# Sheet1.net
KiCad netlist of a schematic drawn in Altium Designer
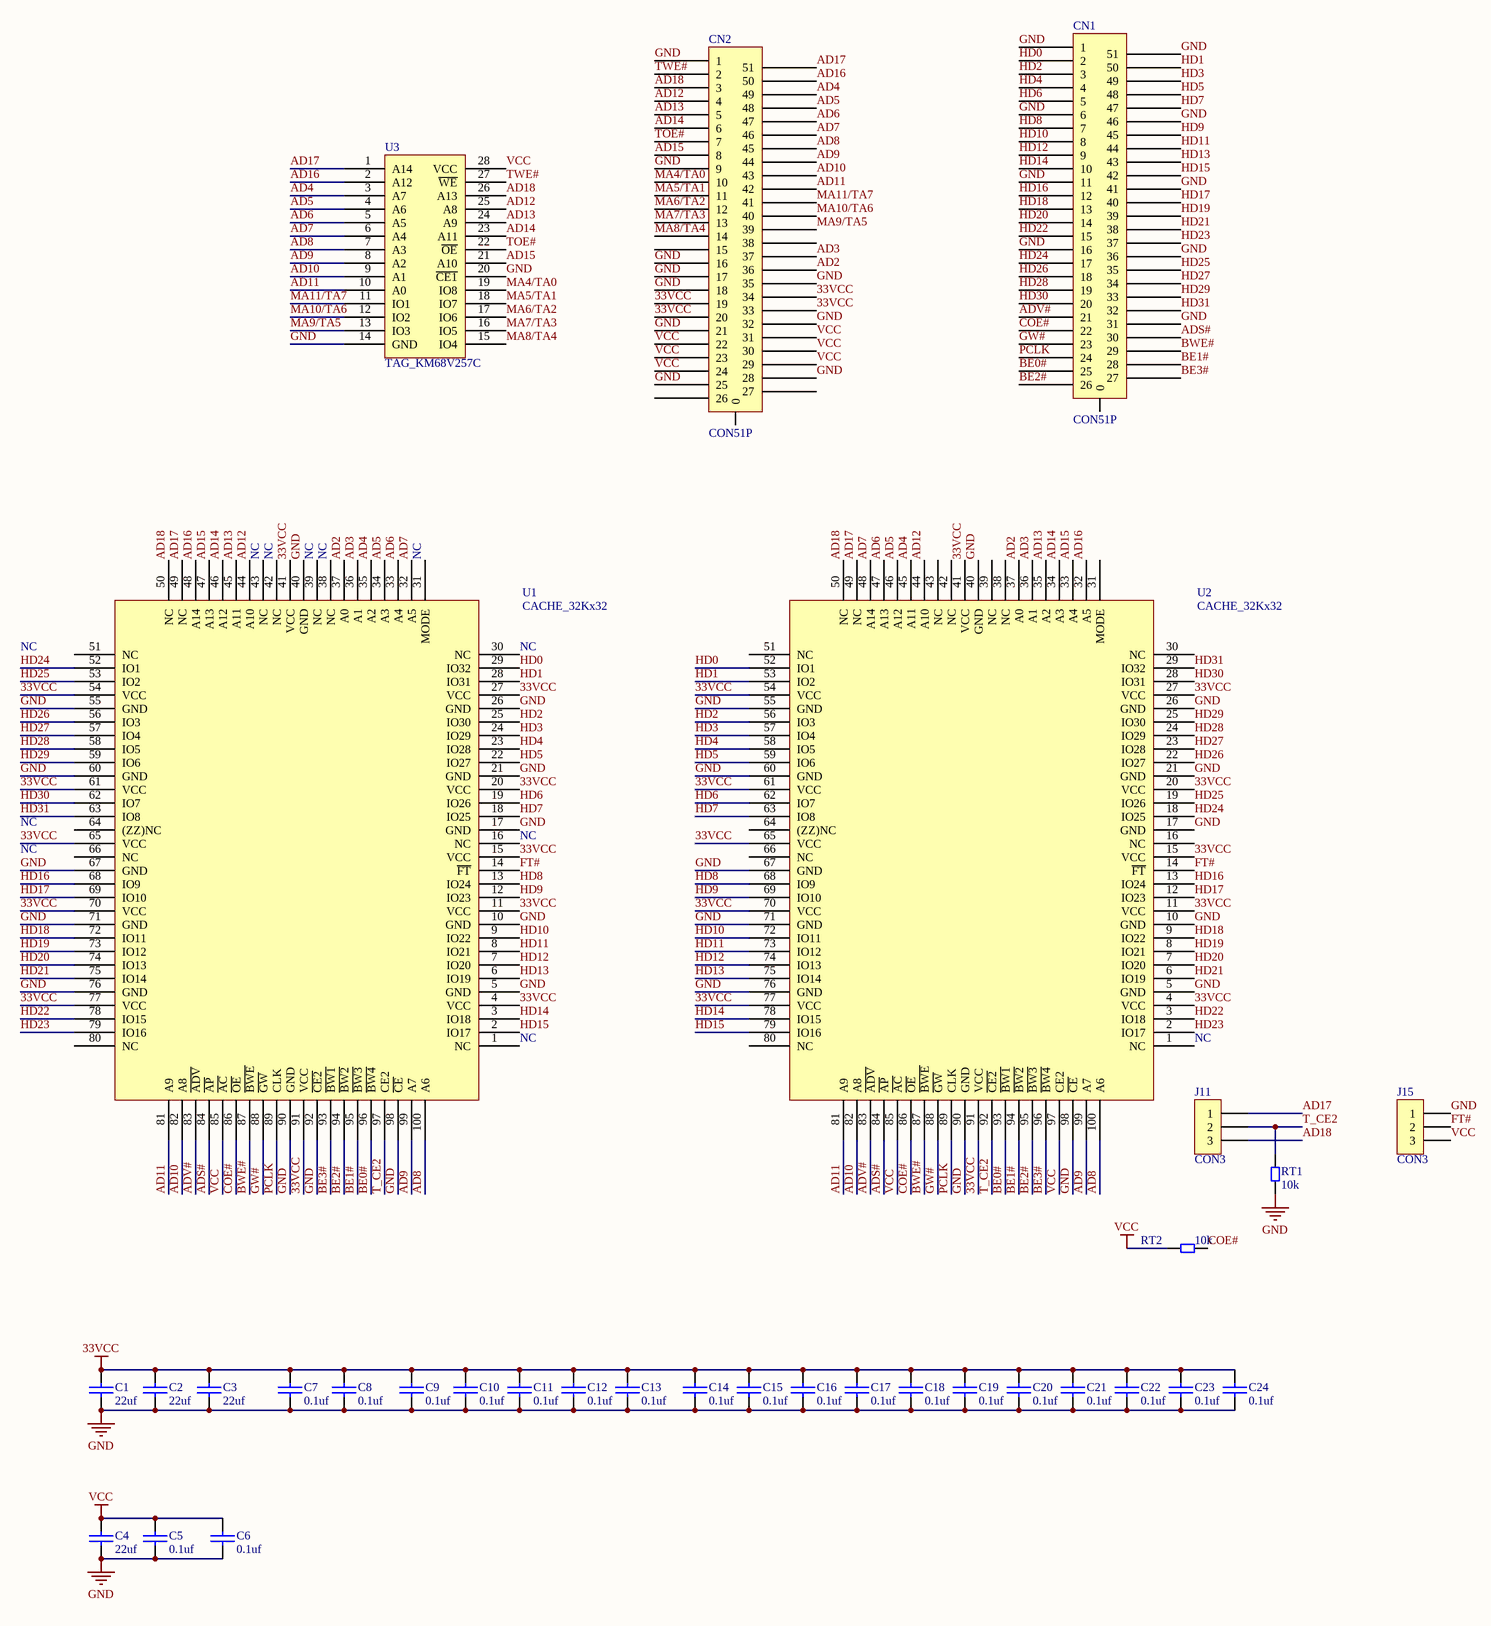
[diagram p0: Sheet1.SchDoc]

(export (version "E")
  (design (tool "Eeschema 10.0.6"))
  (components
    (comp (ref "C1") (value "22uf") (footprint "C0603") (libsource (lib "电阻电容二极管") (part "CAP")))
    (comp (ref "C2") (value "22uf") (footprint "C0603") (libsource (lib "电阻电容二极管") (part "CAP")))
    (comp (ref "C3") (value "22uf") (footprint "C0603") (libsource (lib "电阻电容二极管") (part "CAP")))
    (comp (ref "C4") (value "22uf") (footprint "C0603") (libsource (lib "电阻电容二极管") (part "CAP")))
    (comp (ref "C5") (value "0.1uf") (footprint "C0603") (libsource (lib "电阻电容二极管") (part "CAP")))
    (comp (ref "C6") (value "0.1uf") (footprint "C0603") (libsource (lib "电阻电容二极管") (part "CAP")))
    (comp (ref "C7") (value "0.1uf") (footprint "C0603") (libsource (lib "电阻电容二极管") (part "CAP")))
    (comp (ref "C8") (value "0.1uf") (footprint "C0603") (libsource (lib "电阻电容二极管") (part "CAP")))
    (comp (ref "C9") (value "0.1uf") (footprint "C0603") (libsource (lib "电阻电容二极管") (part "CAP")))
    (comp (ref "C10") (value "0.1uf") (footprint "C0603") (libsource (lib "电阻电容二极管") (part "CAP")))
    (comp (ref "C11") (value "0.1uf") (footprint "C0603") (libsource (lib "电阻电容二极管") (part "CAP")))
    (comp (ref "C12") (value "0.1uf") (footprint "C0603") (libsource (lib "电阻电容二极管") (part "CAP")))
    (comp (ref "C13") (value "0.1uf") (footprint "C0603") (libsource (lib "电阻电容二极管") (part "CAP")))
    (comp (ref "C14") (value "0.1uf") (footprint "C0603") (libsource (lib "电阻电容二极管") (part "CAP")))
    (comp (ref "C15") (value "0.1uf") (footprint "C0603") (libsource (lib "电阻电容二极管") (part "CAP")))
    (comp (ref "C16") (value "0.1uf") (footprint "C0603") (libsource (lib "电阻电容二极管") (part "CAP")))
    (comp (ref "C17") (value "0.1uf") (footprint "C0603") (libsource (lib "电阻电容二极管") (part "CAP")))
    (comp (ref "C18") (value "0.1uf") (footprint "C0603") (libsource (lib "电阻电容二极管") (part "CAP")))
    (comp (ref "C19") (value "0.1uf") (footprint "C0603") (libsource (lib "电阻电容二极管") (part "CAP")))
    (comp (ref "C20") (value "0.1uf") (footprint "C0603") (libsource (lib "电阻电容二极管") (part "CAP")))
    (comp (ref "C21") (value "0.1uf") (footprint "C0603") (libsource (lib "电阻电容二极管") (part "CAP")))
    (comp (ref "C22") (value "0.1uf") (footprint "C0603") (libsource (lib "电阻电容二极管") (part "CAP")))
    (comp (ref "C23") (value "0.1uf") (footprint "C0603") (libsource (lib "电阻电容二极管") (part "CAP")))
    (comp (ref "C24") (value "0.1uf") (footprint "C0603") (libsource (lib "电阻电容二极管") (part "CAP")))
    (comp (ref "CN1") (value "CON51P") (footprint "BTB1.0-51P") (libsource (lib "常用元件库") (part "CON51P")))
    (comp (ref "CN2") (value "CON51P") (footprint "BTB1.0-51P") (libsource (lib "常用元件库") (part "CON51P")))
    (comp (ref "J11") (value "CON3") (footprint "JMP") (libsource (lib "常用元件库") (part "CON3")))
    (comp (ref "J15") (value "CON3") (footprint "JMP") (libsource (lib "常用元件库") (part "CON3")))
    (comp (ref "RT1") (value "10k") (footprint "R0603") (libsource (lib "电阻电容二极管") (part "RES2")))
    (comp (ref "RT2") (value "10k") (footprint "R0603") (libsource (lib "电阻电容二极管") (part "RES2")))
    (comp (ref "U1")
      (value "CACHE_32Kx32")
      (footprint "PQFP100B")
      (libsource (lib "微机原理") (part "CACHE_32Kx32"))
    )
    (comp (ref "U2")
      (value "CACHE_32Kx32")
      (footprint "PQFP100B")
      (libsource (lib "微机原理") (part "CACHE_32Kx32"))
    )
    (comp (ref "U3")
      (value "TAG_KM68V257C")
      (footprint "SOJ-28")
      (libsource (lib "微机原理") (part "TAG_KM68V257C"))
    )
  )
  (nets
    (net (code "1") (name "/AD2") (class "Default")
      (node (ref "CN2") (pin "36") (pinfunction "36_36") (pintype "passive"))
      (node (ref "U1") (pin "37") (pinfunction "A0_37") (pintype "passive"))
      (node (ref "U2") (pin "37") (pinfunction "A0_37") (pintype "passive"))
    )
    (net (code "2") (name "/AD3") (class "Default")
      (node (ref "CN2") (pin "37") (pinfunction "37_37") (pintype "passive"))
      (node (ref "U1") (pin "36") (pinfunction "A1_36") (pintype "passive"))
      (node (ref "U2") (pin "36") (pinfunction "A1_36") (pintype "passive"))
    )
    (net (code "3") (name "/AD4") (class "Default")
      (node (ref "CN2") (pin "49") (pinfunction "49_49") (pintype "passive"))
      (node (ref "U1") (pin "35") (pinfunction "A2_35") (pintype "passive"))
      (node (ref "U2") (pin "45") (pinfunction "A11_45") (pintype "passive"))
      (node (ref "U3") (pin "3") (pinfunction "A7_3") (pintype "passive"))
    )
    (net (code "4") (name "/AD5") (class "Default")
      (node (ref "CN2") (pin "48") (pinfunction "48_48") (pintype "passive"))
      (node (ref "U1") (pin "34") (pinfunction "A3_34") (pintype "passive"))
      (node (ref "U2") (pin "46") (pinfunction "A12_46") (pintype "passive"))
      (node (ref "U3") (pin "4") (pinfunction "A6_4") (pintype "passive"))
    )
    (net (code "5") (name "/AD6") (class "Default")
      (node (ref "CN2") (pin "47") (pinfunction "47_47") (pintype "passive"))
      (node (ref "U1") (pin "33") (pinfunction "A4_33") (pintype "passive"))
      (node (ref "U2") (pin "47") (pinfunction "A13_47") (pintype "passive"))
      (node (ref "U3") (pin "5") (pinfunction "A5_5") (pintype "passive"))
    )
    (net (code "6") (name "/AD7") (class "Default")
      (node (ref "CN2") (pin "46") (pinfunction "46_46") (pintype "passive"))
      (node (ref "U1") (pin "32") (pinfunction "A5_32") (pintype "passive"))
      (node (ref "U2") (pin "48") (pinfunction "A14_48") (pintype "passive"))
      (node (ref "U3") (pin "6") (pinfunction "A4_6") (pintype "passive"))
    )
    (net (code "7") (name "/AD8") (class "Default")
      (node (ref "CN2") (pin "45") (pinfunction "45_45") (pintype "passive"))
      (node (ref "U1") (pin "100") (pinfunction "A6_100") (pintype "passive"))
      (node (ref "U2") (pin "100") (pinfunction "A6_100") (pintype "passive"))
      (node (ref "U3") (pin "7") (pinfunction "A3_7") (pintype "passive"))
    )
    (net (code "8") (name "/AD9") (class "Default")
      (node (ref "CN2") (pin "44") (pinfunction "44_44") (pintype "passive"))
      (node (ref "U1") (pin "99") (pinfunction "A7_99") (pintype "passive"))
      (node (ref "U2") (pin "99") (pinfunction "A7_99") (pintype "passive"))
      (node (ref "U3") (pin "8") (pinfunction "A2_8") (pintype "passive"))
    )
    (net (code "9") (name "/AD10") (class "Default")
      (node (ref "CN2") (pin "43") (pinfunction "43_43") (pintype "passive"))
      (node (ref "U1") (pin "82") (pinfunction "A8_82") (pintype "passive"))
      (node (ref "U2") (pin "82") (pinfunction "A8_82") (pintype "passive"))
      (node (ref "U3") (pin "9") (pinfunction "A1_9") (pintype "passive"))
    )
    (net (code "10") (name "/AD11") (class "Default")
      (node (ref "CN2") (pin "42") (pinfunction "42_42") (pintype "passive"))
      (node (ref "U1") (pin "81") (pinfunction "A9_81") (pintype "passive"))
      (node (ref "U2") (pin "81") (pinfunction "A9_81") (pintype "passive"))
      (node (ref "U3") (pin "10") (pinfunction "A0_10") (pintype "passive"))
    )
    (net (code "11") (name "/AD12") (class "Default")
      (node (ref "CN2") (pin "4") (pinfunction "4_4") (pintype "passive"))
      (node (ref "U1") (pin "44") (pinfunction "A10_44") (pintype "passive"))
      (node (ref "U2") (pin "44") (pinfunction "A10_44") (pintype "passive"))
      (node (ref "U3") (pin "25") (pinfunction "A8_25") (pintype "passive"))
    )
    (net (code "12") (name "/AD13") (class "Default")
      (node (ref "CN2") (pin "5") (pinfunction "5_5") (pintype "passive"))
      (node (ref "U1") (pin "45") (pinfunction "A11_45") (pintype "passive"))
      (node (ref "U2") (pin "35") (pinfunction "A2_35") (pintype "passive"))
      (node (ref "U3") (pin "24") (pinfunction "A9_24") (pintype "passive"))
    )
    (net (code "13") (name "/AD14") (class "Default")
      (node (ref "CN2") (pin "6") (pinfunction "6_6") (pintype "passive"))
      (node (ref "U1") (pin "46") (pinfunction "A12_46") (pintype "passive"))
      (node (ref "U2") (pin "34") (pinfunction "A3_34") (pintype "passive"))
      (node (ref "U3") (pin "23") (pinfunction "A11_23") (pintype "passive"))
    )
    (net (code "14") (name "/AD15") (class "Default")
      (node (ref "CN2") (pin "8") (pinfunction "8_8") (pintype "passive"))
      (node (ref "U1") (pin "47") (pinfunction "A13_47") (pintype "passive"))
      (node (ref "U2") (pin "33") (pinfunction "A4_33") (pintype "passive"))
      (node (ref "U3") (pin "21") (pinfunction "A10_21") (pintype "passive"))
    )
    (net (code "15") (name "/AD16") (class "Default")
      (node (ref "CN2") (pin "50") (pinfunction "50_50") (pintype "passive"))
      (node (ref "U1") (pin "48") (pinfunction "A14_48") (pintype "passive"))
      (node (ref "U2") (pin "32") (pinfunction "A5_32") (pintype "passive"))
      (node (ref "U3") (pin "2") (pinfunction "A12_2") (pintype "passive"))
    )
    (net (code "16") (name "/AD17") (class "Default")
      (node (ref "CN2") (pin "51") (pinfunction "51_51") (pintype "passive"))
      (node (ref "J11") (pin "1") (pinfunction "1_1") (pintype "passive"))
      (node (ref "U1") (pin "49") (pinfunction "NC_49") (pintype "passive"))
      (node (ref "U2") (pin "49") (pinfunction "NC_49") (pintype "passive"))
      (node (ref "U3") (pin "1") (pinfunction "A14_1") (pintype "passive"))
    )
    (net (code "17") (name "/AD18") (class "Default")
      (node (ref "CN2") (pin "3") (pinfunction "3_3") (pintype "passive"))
      (node (ref "J11") (pin "3") (pinfunction "3_3") (pintype "passive"))
      (node (ref "U1") (pin "50") (pinfunction "NC_50") (pintype "passive"))
      (node (ref "U2") (pin "50") (pinfunction "NC_50") (pintype "passive"))
      (node (ref "U3") (pin "26") (pinfunction "A13_26") (pintype "passive"))
    )
    (net (code "18") (name "/ADS#") (class "Default")
      (node (ref "CN1") (pin "30") (pinfunction "30_30") (pintype "passive"))
      (node (ref "U1") (pin "84") (pinfunction "~{AP}_84") (pintype "passive"))
      (node (ref "U2") (pin "84") (pinfunction "~{AP}_84") (pintype "passive"))
    )
    (net (code "19") (name "/ADV#") (class "Default")
      (node (ref "CN1") (pin "21") (pinfunction "21_21") (pintype "passive"))
      (node (ref "U1") (pin "83") (pinfunction "~{ADV}_83") (pintype "passive"))
      (node (ref "U2") (pin "83") (pinfunction "~{ADV}_83") (pintype "passive"))
    )
    (net (code "20") (name "/BE0#") (class "Default")
      (node (ref "CN1") (pin "25") (pinfunction "25_25") (pintype "passive"))
      (node (ref "U1") (pin "96") (pinfunction "~{BW4}_96") (pintype "passive"))
      (node (ref "U2") (pin "93") (pinfunction "~{BW1}_93") (pintype "passive"))
    )
    (net (code "21") (name "/BE1#") (class "Default")
      (node (ref "CN1") (pin "28") (pinfunction "28_28") (pintype "passive"))
      (node (ref "U1") (pin "95") (pinfunction "~{BW3}_95") (pintype "passive"))
      (node (ref "U2") (pin "94") (pinfunction "~{BW2}_94") (pintype "passive"))
    )
    (net (code "22") (name "/BE2#") (class "Default")
      (node (ref "CN1") (pin "26") (pinfunction "26_26") (pintype "passive"))
      (node (ref "U1") (pin "94") (pinfunction "~{BW2}_94") (pintype "passive"))
      (node (ref "U2") (pin "95") (pinfunction "~{BW3}_95") (pintype "passive"))
    )
    (net (code "23") (name "/BE3#") (class "Default")
      (node (ref "CN1") (pin "27") (pinfunction "27_27") (pintype "passive"))
      (node (ref "U1") (pin "93") (pinfunction "~{BW1}_93") (pintype "passive"))
      (node (ref "U2") (pin "96") (pinfunction "~{BW4}_96") (pintype "passive"))
    )
    (net (code "24") (name "/BWE#") (class "Default")
      (node (ref "CN1") (pin "29") (pinfunction "29_29") (pintype "passive"))
      (node (ref "U1") (pin "87") (pinfunction "~{BWE}_87") (pintype "passive"))
      (node (ref "U2") (pin "87") (pinfunction "~{BWE}_87") (pintype "passive"))
    )
    (net (code "25") (name "/COE#") (class "Default")
      (node (ref "CN1") (pin "22") (pinfunction "22_22") (pintype "passive"))
      (node (ref "RT2") (pin "1") (pinfunction "1_1") (pintype "passive"))
      (node (ref "U1") (pin "86") (pinfunction "~{OE}_86") (pintype "passive"))
      (node (ref "U2") (pin "86") (pinfunction "~{OE}_86") (pintype "passive"))
    )
    (net (code "26") (name "/FT#") (class "Default")
      (node (ref "J15") (pin "2") (pinfunction "2_2") (pintype "passive"))
      (node (ref "U1") (pin "14") (pinfunction "~{FT}_14") (pintype "passive"))
      (node (ref "U2") (pin "14") (pinfunction "~{FT}_14") (pintype "passive"))
    )
    (net (code "27") (name "/GW#") (class "Default")
      (node (ref "CN1") (pin "23") (pinfunction "23_23") (pintype "passive"))
      (node (ref "U1") (pin "88") (pinfunction "~{GW}_88") (pintype "passive"))
      (node (ref "U2") (pin "88") (pinfunction "~{GW}_88") (pintype "passive"))
    )
    (net (code "28") (name "/HD0") (class "Default")
      (node (ref "CN1") (pin "2") (pinfunction "2_2") (pintype "passive"))
      (node (ref "U1") (pin "29") (pinfunction "IO32_29") (pintype "passive"))
      (node (ref "U2") (pin "52") (pinfunction "IO1_52") (pintype "passive"))
    )
    (net (code "29") (name "/HD1") (class "Default")
      (node (ref "CN1") (pin "50") (pinfunction "50_50") (pintype "passive"))
      (node (ref "U1") (pin "28") (pinfunction "IO31_28") (pintype "passive"))
      (node (ref "U2") (pin "53") (pinfunction "IO2_53") (pintype "passive"))
    )
    (net (code "30") (name "/HD2") (class "Default")
      (node (ref "CN1") (pin "3") (pinfunction "3_3") (pintype "passive"))
      (node (ref "U1") (pin "25") (pinfunction "IO30_25") (pintype "passive"))
      (node (ref "U2") (pin "56") (pinfunction "IO3_56") (pintype "passive"))
    )
    (net (code "31") (name "/HD3") (class "Default")
      (node (ref "CN1") (pin "49") (pinfunction "49_49") (pintype "passive"))
      (node (ref "U1") (pin "24") (pinfunction "IO29_24") (pintype "passive"))
      (node (ref "U2") (pin "57") (pinfunction "IO4_57") (pintype "passive"))
    )
    (net (code "32") (name "/HD4") (class "Default")
      (node (ref "CN1") (pin "4") (pinfunction "4_4") (pintype "passive"))
      (node (ref "U1") (pin "23") (pinfunction "IO28_23") (pintype "passive"))
      (node (ref "U2") (pin "58") (pinfunction "IO5_58") (pintype "passive"))
    )
    (net (code "33") (name "/HD5") (class "Default")
      (node (ref "CN1") (pin "48") (pinfunction "48_48") (pintype "passive"))
      (node (ref "U1") (pin "22") (pinfunction "IO27_22") (pintype "passive"))
      (node (ref "U2") (pin "59") (pinfunction "IO6_59") (pintype "passive"))
    )
    (net (code "34") (name "/HD6") (class "Default")
      (node (ref "CN1") (pin "5") (pinfunction "5_5") (pintype "passive"))
      (node (ref "U1") (pin "19") (pinfunction "IO26_19") (pintype "passive"))
      (node (ref "U2") (pin "62") (pinfunction "IO7_62") (pintype "passive"))
    )
    (net (code "35") (name "/HD7") (class "Default")
      (node (ref "CN1") (pin "47") (pinfunction "47_47") (pintype "passive"))
      (node (ref "U1") (pin "18") (pinfunction "IO25_18") (pintype "passive"))
      (node (ref "U2") (pin "63") (pinfunction "IO8_63") (pintype "passive"))
    )
    (net (code "36") (name "/HD8") (class "Default")
      (node (ref "CN1") (pin "7") (pinfunction "7_7") (pintype "passive"))
      (node (ref "U1") (pin "13") (pinfunction "IO24_13") (pintype "passive"))
      (node (ref "U2") (pin "68") (pinfunction "IO9_68") (pintype "passive"))
    )
    (net (code "37") (name "/HD9") (class "Default")
      (node (ref "CN1") (pin "45") (pinfunction "45_45") (pintype "passive"))
      (node (ref "U1") (pin "12") (pinfunction "IO23_12") (pintype "passive"))
      (node (ref "U2") (pin "69") (pinfunction "IO10_69") (pintype "passive"))
    )
    (net (code "38") (name "/HD10") (class "Default")
      (node (ref "CN1") (pin "8") (pinfunction "8_8") (pintype "passive"))
      (node (ref "U1") (pin "9") (pinfunction "IO22_9") (pintype "passive"))
      (node (ref "U2") (pin "72") (pinfunction "IO11_72") (pintype "passive"))
    )
    (net (code "39") (name "/HD11") (class "Default")
      (node (ref "CN1") (pin "44") (pinfunction "44_44") (pintype "passive"))
      (node (ref "U1") (pin "8") (pinfunction "IO21_8") (pintype "passive"))
      (node (ref "U2") (pin "73") (pinfunction "IO12_73") (pintype "passive"))
    )
    (net (code "40") (name "/HD12") (class "Default")
      (node (ref "CN1") (pin "9") (pinfunction "9_9") (pintype "passive"))
      (node (ref "U1") (pin "7") (pinfunction "IO20_7") (pintype "passive"))
      (node (ref "U2") (pin "74") (pinfunction "IO13_74") (pintype "passive"))
    )
    (net (code "41") (name "/HD13") (class "Default")
      (node (ref "CN1") (pin "43") (pinfunction "43_43") (pintype "passive"))
      (node (ref "U1") (pin "6") (pinfunction "IO19_6") (pintype "passive"))
      (node (ref "U2") (pin "75") (pinfunction "IO14_75") (pintype "passive"))
    )
    (net (code "42") (name "/HD14") (class "Default")
      (node (ref "CN1") (pin "10") (pinfunction "10_10") (pintype "passive"))
      (node (ref "U1") (pin "3") (pinfunction "IO18_3") (pintype "passive"))
      (node (ref "U2") (pin "78") (pinfunction "IO15_78") (pintype "passive"))
    )
    (net (code "43") (name "/HD15") (class "Default")
      (node (ref "CN1") (pin "42") (pinfunction "42_42") (pintype "passive"))
      (node (ref "U1") (pin "2") (pinfunction "IO17_2") (pintype "passive"))
      (node (ref "U2") (pin "79") (pinfunction "IO16_79") (pintype "passive"))
    )
    (net (code "44") (name "/HD16") (class "Default")
      (node (ref "CN1") (pin "12") (pinfunction "12_12") (pintype "passive"))
      (node (ref "U1") (pin "68") (pinfunction "IO9_68") (pintype "passive"))
      (node (ref "U2") (pin "13") (pinfunction "IO24_13") (pintype "passive"))
    )
    (net (code "45") (name "/HD17") (class "Default")
      (node (ref "CN1") (pin "40") (pinfunction "40_40") (pintype "passive"))
      (node (ref "U1") (pin "69") (pinfunction "IO10_69") (pintype "passive"))
      (node (ref "U2") (pin "12") (pinfunction "IO23_12") (pintype "passive"))
    )
    (net (code "46") (name "/HD18") (class "Default")
      (node (ref "CN1") (pin "13") (pinfunction "13_13") (pintype "passive"))
      (node (ref "U1") (pin "72") (pinfunction "IO11_72") (pintype "passive"))
      (node (ref "U2") (pin "9") (pinfunction "IO22_9") (pintype "passive"))
    )
    (net (code "47") (name "/HD19") (class "Default")
      (node (ref "CN1") (pin "39") (pinfunction "39_39") (pintype "passive"))
      (node (ref "U1") (pin "73") (pinfunction "IO12_73") (pintype "passive"))
      (node (ref "U2") (pin "8") (pinfunction "IO21_8") (pintype "passive"))
    )
    (net (code "48") (name "/HD20") (class "Default")
      (node (ref "CN1") (pin "14") (pinfunction "14_14") (pintype "passive"))
      (node (ref "U1") (pin "74") (pinfunction "IO13_74") (pintype "passive"))
      (node (ref "U2") (pin "7") (pinfunction "IO20_7") (pintype "passive"))
    )
    (net (code "49") (name "/HD21") (class "Default")
      (node (ref "CN1") (pin "38") (pinfunction "38_38") (pintype "passive"))
      (node (ref "U1") (pin "75") (pinfunction "IO14_75") (pintype "passive"))
      (node (ref "U2") (pin "6") (pinfunction "IO19_6") (pintype "passive"))
    )
    (net (code "50") (name "/HD22") (class "Default")
      (node (ref "CN1") (pin "15") (pinfunction "15_15") (pintype "passive"))
      (node (ref "U1") (pin "78") (pinfunction "IO15_78") (pintype "passive"))
      (node (ref "U2") (pin "3") (pinfunction "IO18_3") (pintype "passive"))
    )
    (net (code "51") (name "/HD23") (class "Default")
      (node (ref "CN1") (pin "37") (pinfunction "37_37") (pintype "passive"))
      (node (ref "U1") (pin "79") (pinfunction "IO16_79") (pintype "passive"))
      (node (ref "U2") (pin "2") (pinfunction "IO17_2") (pintype "passive"))
    )
    (net (code "52") (name "/HD24") (class "Default")
      (node (ref "CN1") (pin "17") (pinfunction "17_17") (pintype "passive"))
      (node (ref "U1") (pin "52") (pinfunction "IO1_52") (pintype "passive"))
      (node (ref "U2") (pin "18") (pinfunction "IO25_18") (pintype "passive"))
    )
    (net (code "53") (name "/HD25") (class "Default")
      (node (ref "CN1") (pin "35") (pinfunction "35_35") (pintype "passive"))
      (node (ref "U1") (pin "53") (pinfunction "IO2_53") (pintype "passive"))
      (node (ref "U2") (pin "19") (pinfunction "IO26_19") (pintype "passive"))
    )
    (net (code "54") (name "/HD26") (class "Default")
      (node (ref "CN1") (pin "18") (pinfunction "18_18") (pintype "passive"))
      (node (ref "U1") (pin "56") (pinfunction "IO3_56") (pintype "passive"))
      (node (ref "U2") (pin "22") (pinfunction "IO27_22") (pintype "passive"))
    )
    (net (code "55") (name "/HD27") (class "Default")
      (node (ref "CN1") (pin "34") (pinfunction "34_34") (pintype "passive"))
      (node (ref "U1") (pin "57") (pinfunction "IO4_57") (pintype "passive"))
      (node (ref "U2") (pin "23") (pinfunction "IO28_23") (pintype "passive"))
    )
    (net (code "56") (name "/HD28") (class "Default")
      (node (ref "CN1") (pin "19") (pinfunction "19_19") (pintype "passive"))
      (node (ref "U1") (pin "58") (pinfunction "IO5_58") (pintype "passive"))
      (node (ref "U2") (pin "24") (pinfunction "IO29_24") (pintype "passive"))
    )
    (net (code "57") (name "/HD29") (class "Default")
      (node (ref "CN1") (pin "33") (pinfunction "33_33") (pintype "passive"))
      (node (ref "U1") (pin "59") (pinfunction "IO6_59") (pintype "passive"))
      (node (ref "U2") (pin "25") (pinfunction "IO30_25") (pintype "passive"))
    )
    (net (code "58") (name "/HD30") (class "Default")
      (node (ref "CN1") (pin "20") (pinfunction "20_20") (pintype "passive"))
      (node (ref "U1") (pin "62") (pinfunction "IO7_62") (pintype "passive"))
      (node (ref "U2") (pin "28") (pinfunction "IO31_28") (pintype "passive"))
    )
    (net (code "59") (name "/HD31") (class "Default")
      (node (ref "CN1") (pin "32") (pinfunction "32_32") (pintype "passive"))
      (node (ref "U1") (pin "63") (pinfunction "IO8_63") (pintype "passive"))
      (node (ref "U2") (pin "29") (pinfunction "IO32_29") (pintype "passive"))
    )
    (net (code "60") (name "/MA4{slash}TA0") (class "Default")
      (node (ref "CN2") (pin "10") (pinfunction "10_10") (pintype "passive"))
      (node (ref "U3") (pin "19") (pinfunction "IO8_19") (pintype "passive"))
    )
    (net (code "61") (name "/MA5{slash}TA1") (class "Default")
      (node (ref "CN2") (pin "11") (pinfunction "11_11") (pintype "passive"))
      (node (ref "U3") (pin "18") (pinfunction "IO7_18") (pintype "passive"))
    )
    (net (code "62") (name "/MA6{slash}TA2") (class "Default")
      (node (ref "CN2") (pin "12") (pinfunction "12_12") (pintype "passive"))
      (node (ref "U3") (pin "17") (pinfunction "IO6_17") (pintype "passive"))
    )
    (net (code "63") (name "/MA7{slash}TA3") (class "Default")
      (node (ref "CN2") (pin "13") (pinfunction "13_13") (pintype "passive"))
      (node (ref "U3") (pin "16") (pinfunction "IO5_16") (pintype "passive"))
    )
    (net (code "64") (name "/MA8{slash}TA4") (class "Default")
      (node (ref "CN2") (pin "14") (pinfunction "14_14") (pintype "passive"))
      (node (ref "U3") (pin "15") (pinfunction "IO4_15") (pintype "passive"))
    )
    (net (code "65") (name "/MA9{slash}TA5") (class "Default")
      (node (ref "CN2") (pin "39") (pinfunction "39_39") (pintype "passive"))
      (node (ref "U3") (pin "13") (pinfunction "IO3_13") (pintype "passive"))
    )
    (net (code "66") (name "/MA10{slash}TA6") (class "Default")
      (node (ref "CN2") (pin "40") (pinfunction "40_40") (pintype "passive"))
      (node (ref "U3") (pin "12") (pinfunction "IO2_12") (pintype "passive"))
    )
    (net (code "67") (name "/MA11{slash}TA7") (class "Default")
      (node (ref "CN2") (pin "41") (pinfunction "41_41") (pintype "passive"))
      (node (ref "U3") (pin "11") (pinfunction "IO1_11") (pintype "passive"))
    )
    (net (code "68") (name "/PCLK") (class "Default")
      (node (ref "CN1") (pin "24") (pinfunction "24_24") (pintype "passive"))
      (node (ref "U1") (pin "89") (pinfunction "CLK_89") (pintype "passive"))
      (node (ref "U2") (pin "89") (pinfunction "CLK_89") (pintype "passive"))
    )
    (net (code "69") (name "/TOE#") (class "Default")
      (node (ref "CN2") (pin "7") (pinfunction "7_7") (pintype "passive"))
      (node (ref "U3") (pin "22") (pinfunction "~{OE}_22") (pintype "passive"))
    )
    (net (code "70") (name "/TWE#") (class "Default")
      (node (ref "CN2") (pin "2") (pinfunction "2_2") (pintype "passive"))
      (node (ref "U3") (pin "27") (pinfunction "~{WE}_27") (pintype "passive"))
    )
    (net (code "71") (name "/T_CE2") (class "Default")
      (node (ref "J11") (pin "2") (pinfunction "2_2") (pintype "passive"))
      (node (ref "RT1") (pin "1") (pinfunction "1_1") (pintype "passive"))
      (node (ref "U1") (pin "97") (pinfunction "CE2_97") (pintype "passive"))
      (node (ref "U2") (pin "92") (pinfunction "~{CE2}_92") (pintype "passive"))
    )
    (net (code "72") (name "33VCC") (class "Default")
      (node (ref "C1") (pin "1") (pinfunction "1_1") (pintype "passive"))
      (node (ref "C10") (pin "1") (pinfunction "1_1") (pintype "passive"))
      (node (ref "C11") (pin "1") (pinfunction "1_1") (pintype "passive"))
      (node (ref "C12") (pin "1") (pinfunction "1_1") (pintype "passive"))
      (node (ref "C13") (pin "1") (pinfunction "1_1") (pintype "passive"))
      (node (ref "C14") (pin "1") (pinfunction "1_1") (pintype "passive"))
      (node (ref "C15") (pin "1") (pinfunction "1_1") (pintype "passive"))
      (node (ref "C16") (pin "1") (pinfunction "1_1") (pintype "passive"))
      (node (ref "C17") (pin "1") (pinfunction "1_1") (pintype "passive"))
      (node (ref "C18") (pin "1") (pinfunction "1_1") (pintype "passive"))
      (node (ref "C19") (pin "1") (pinfunction "1_1") (pintype "passive"))
      (node (ref "C2") (pin "1") (pinfunction "1_1") (pintype "passive"))
      (node (ref "C20") (pin "1") (pinfunction "1_1") (pintype "passive"))
      (node (ref "C21") (pin "1") (pinfunction "1_1") (pintype "passive"))
      (node (ref "C22") (pin "1") (pinfunction "1_1") (pintype "passive"))
      (node (ref "C23") (pin "1") (pinfunction "1_1") (pintype "passive"))
      (node (ref "C24") (pin "1") (pinfunction "1_1") (pintype "passive"))
      (node (ref "C3") (pin "1") (pinfunction "1_1") (pintype "passive"))
      (node (ref "C7") (pin "1") (pinfunction "1_1") (pintype "passive"))
      (node (ref "C8") (pin "1") (pinfunction "1_1") (pintype "passive"))
      (node (ref "C9") (pin "1") (pinfunction "1_1") (pintype "passive"))
      (node (ref "CN2") (pin "19") (pinfunction "19_19") (pintype "passive"))
      (node (ref "CN2") (pin "20") (pinfunction "20_20") (pintype "passive"))
      (node (ref "CN2") (pin "33") (pinfunction "33_33") (pintype "passive"))
      (node (ref "CN2") (pin "34") (pinfunction "34_34") (pintype "passive"))
      (node (ref "U1") (pin "11") (pinfunction "VCC_11") (pintype "passive"))
      (node (ref "U1") (pin "15") (pinfunction "VCC_15") (pintype "passive"))
      (node (ref "U1") (pin "20") (pinfunction "VCC_20") (pintype "passive"))
      (node (ref "U1") (pin "27") (pinfunction "VCC_27") (pintype "passive"))
      (node (ref "U1") (pin "4") (pinfunction "VCC_4") (pintype "passive"))
      (node (ref "U1") (pin "41") (pinfunction "VCC_41") (pintype "passive"))
      (node (ref "U1") (pin "54") (pinfunction "VCC_54") (pintype "passive"))
      (node (ref "U1") (pin "61") (pinfunction "VCC_61") (pintype "passive"))
      (node (ref "U1") (pin "65") (pinfunction "VCC_65") (pintype "passive"))
      (node (ref "U1") (pin "70") (pinfunction "VCC_70") (pintype "passive"))
      (node (ref "U1") (pin "77") (pinfunction "VCC_77") (pintype "passive"))
      (node (ref "U1") (pin "91") (pinfunction "VCC_91") (pintype "passive"))
      (node (ref "U2") (pin "11") (pinfunction "VCC_11") (pintype "passive"))
      (node (ref "U2") (pin "15") (pinfunction "VCC_15") (pintype "passive"))
      (node (ref "U2") (pin "20") (pinfunction "VCC_20") (pintype "passive"))
      (node (ref "U2") (pin "27") (pinfunction "VCC_27") (pintype "passive"))
      (node (ref "U2") (pin "4") (pinfunction "VCC_4") (pintype "passive"))
      (node (ref "U2") (pin "41") (pinfunction "VCC_41") (pintype "passive"))
      (node (ref "U2") (pin "54") (pinfunction "VCC_54") (pintype "passive"))
      (node (ref "U2") (pin "61") (pinfunction "VCC_61") (pintype "passive"))
      (node (ref "U2") (pin "65") (pinfunction "VCC_65") (pintype "passive"))
      (node (ref "U2") (pin "70") (pinfunction "VCC_70") (pintype "passive"))
      (node (ref "U2") (pin "77") (pinfunction "VCC_77") (pintype "passive"))
      (node (ref "U2") (pin "91") (pinfunction "VCC_91") (pintype "passive"))
    )
    (net (code "73") (name "GND") (class "Default")
      (node (ref "C1") (pin "2") (pinfunction "2_2") (pintype "passive"))
      (node (ref "C10") (pin "2") (pinfunction "2_2") (pintype "passive"))
      (node (ref "C11") (pin "2") (pinfunction "2_2") (pintype "passive"))
      (node (ref "C12") (pin "2") (pinfunction "2_2") (pintype "passive"))
      (node (ref "C13") (pin "2") (pinfunction "2_2") (pintype "passive"))
      (node (ref "C14") (pin "2") (pinfunction "2_2") (pintype "passive"))
      (node (ref "C15") (pin "2") (pinfunction "2_2") (pintype "passive"))
      (node (ref "C16") (pin "2") (pinfunction "2_2") (pintype "passive"))
      (node (ref "C17") (pin "2") (pinfunction "2_2") (pintype "passive"))
      (node (ref "C18") (pin "2") (pinfunction "2_2") (pintype "passive"))
      (node (ref "C19") (pin "2") (pinfunction "2_2") (pintype "passive"))
      (node (ref "C2") (pin "2") (pinfunction "2_2") (pintype "passive"))
      (node (ref "C20") (pin "2") (pinfunction "2_2") (pintype "passive"))
      (node (ref "C21") (pin "2") (pinfunction "2_2") (pintype "passive"))
      (node (ref "C22") (pin "2") (pinfunction "2_2") (pintype "passive"))
      (node (ref "C23") (pin "2") (pinfunction "2_2") (pintype "passive"))
      (node (ref "C24") (pin "2") (pinfunction "2_2") (pintype "passive"))
      (node (ref "C3") (pin "2") (pinfunction "2_2") (pintype "passive"))
      (node (ref "C4") (pin "2") (pinfunction "2_2") (pintype "passive"))
      (node (ref "C5") (pin "2") (pinfunction "2_2") (pintype "passive"))
      (node (ref "C6") (pin "2") (pinfunction "2_2") (pintype "passive"))
      (node (ref "C7") (pin "2") (pinfunction "2_2") (pintype "passive"))
      (node (ref "C8") (pin "2") (pinfunction "2_2") (pintype "passive"))
      (node (ref "C9") (pin "2") (pinfunction "2_2") (pintype "passive"))
      (node (ref "CN1") (pin "1") (pinfunction "1_1") (pintype "passive"))
      (node (ref "CN1") (pin "11") (pinfunction "11_11") (pintype "passive"))
      (node (ref "CN1") (pin "16") (pinfunction "16_16") (pintype "passive"))
      (node (ref "CN1") (pin "31") (pinfunction "31_31") (pintype "passive"))
      (node (ref "CN1") (pin "36") (pinfunction "36_36") (pintype "passive"))
      (node (ref "CN1") (pin "41") (pinfunction "41_41") (pintype "passive"))
      (node (ref "CN1") (pin "46") (pinfunction "46_46") (pintype "passive"))
      (node (ref "CN1") (pin "51") (pinfunction "51_51") (pintype "passive"))
      (node (ref "CN1") (pin "6") (pinfunction "6_6") (pintype "passive"))
      (node (ref "CN2") (pin "1") (pinfunction "1_1") (pintype "passive"))
      (node (ref "CN2") (pin "16") (pinfunction "16_16") (pintype "passive"))
      (node (ref "CN2") (pin "17") (pinfunction "17_17") (pintype "passive"))
      (node (ref "CN2") (pin "18") (pinfunction "18_18") (pintype "passive"))
      (node (ref "CN2") (pin "21") (pinfunction "21_21") (pintype "passive"))
      (node (ref "CN2") (pin "25") (pinfunction "25_25") (pintype "passive"))
      (node (ref "CN2") (pin "28") (pinfunction "28_28") (pintype "passive"))
      (node (ref "CN2") (pin "32") (pinfunction "32_32") (pintype "passive"))
      (node (ref "CN2") (pin "35") (pinfunction "35_35") (pintype "passive"))
      (node (ref "CN2") (pin "9") (pinfunction "9_9") (pintype "passive"))
      (node (ref "J15") (pin "1") (pinfunction "1_1") (pintype "passive"))
      (node (ref "RT1") (pin "2") (pinfunction "2_2") (pintype "passive"))
      (node (ref "U1") (pin "10") (pinfunction "GND_10") (pintype "passive"))
      (node (ref "U1") (pin "17") (pinfunction "GND_17") (pintype "passive"))
      (node (ref "U1") (pin "21") (pinfunction "GND_21") (pintype "passive"))
      (node (ref "U1") (pin "26") (pinfunction "GND_26") (pintype "passive"))
      (node (ref "U1") (pin "40") (pinfunction "GND_40") (pintype "passive"))
      (node (ref "U1") (pin "5") (pinfunction "GND_5") (pintype "passive"))
      (node (ref "U1") (pin "55") (pinfunction "GND_55") (pintype "passive"))
      (node (ref "U1") (pin "60") (pinfunction "GND_60") (pintype "passive"))
      (node (ref "U1") (pin "67") (pinfunction "GND_67") (pintype "passive"))
      (node (ref "U1") (pin "71") (pinfunction "GND_71") (pintype "passive"))
      (node (ref "U1") (pin "76") (pinfunction "GND_76") (pintype "passive"))
      (node (ref "U1") (pin "90") (pinfunction "GND_90") (pintype "passive"))
      (node (ref "U1") (pin "92") (pinfunction "~{CE2}_92") (pintype "passive"))
      (node (ref "U1") (pin "98") (pinfunction "~{CE}_98") (pintype "passive"))
      (node (ref "U2") (pin "10") (pinfunction "GND_10") (pintype "passive"))
      (node (ref "U2") (pin "17") (pinfunction "GND_17") (pintype "passive"))
      (node (ref "U2") (pin "21") (pinfunction "GND_21") (pintype "passive"))
      (node (ref "U2") (pin "26") (pinfunction "GND_26") (pintype "passive"))
      (node (ref "U2") (pin "40") (pinfunction "GND_40") (pintype "passive"))
      (node (ref "U2") (pin "5") (pinfunction "GND_5") (pintype "passive"))
      (node (ref "U2") (pin "55") (pinfunction "GND_55") (pintype "passive"))
      (node (ref "U2") (pin "60") (pinfunction "GND_60") (pintype "passive"))
      (node (ref "U2") (pin "67") (pinfunction "GND_67") (pintype "passive"))
      (node (ref "U2") (pin "71") (pinfunction "GND_71") (pintype "passive"))
      (node (ref "U2") (pin "76") (pinfunction "GND_76") (pintype "passive"))
      (node (ref "U2") (pin "90") (pinfunction "GND_90") (pintype "passive"))
      (node (ref "U2") (pin "98") (pinfunction "~{CE}_98") (pintype "passive"))
      (node (ref "U3") (pin "14") (pinfunction "GND_14") (pintype "passive"))
      (node (ref "U3") (pin "20") (pinfunction "~{CE1}_20") (pintype "passive"))
    )
    (net (code "74") (name "VCC") (class "Default")
      (node (ref "C4") (pin "1") (pinfunction "1_1") (pintype "passive"))
      (node (ref "C5") (pin "1") (pinfunction "1_1") (pintype "passive"))
      (node (ref "C6") (pin "1") (pinfunction "1_1") (pintype "passive"))
      (node (ref "CN2") (pin "22") (pinfunction "22_22") (pintype "passive"))
      (node (ref "CN2") (pin "23") (pinfunction "23_23") (pintype "passive"))
      (node (ref "CN2") (pin "24") (pinfunction "24_24") (pintype "passive"))
      (node (ref "CN2") (pin "29") (pinfunction "29_29") (pintype "passive"))
      (node (ref "CN2") (pin "30") (pinfunction "30_30") (pintype "passive"))
      (node (ref "CN2") (pin "31") (pinfunction "31_31") (pintype "passive"))
      (node (ref "J15") (pin "3") (pinfunction "3_3") (pintype "passive"))
      (node (ref "RT2") (pin "2") (pinfunction "2_2") (pintype "passive"))
      (node (ref "U1") (pin "85") (pinfunction "~{AC}_85") (pintype "passive"))
      (node (ref "U2") (pin "85") (pinfunction "~{AC}_85") (pintype "passive"))
      (node (ref "U2") (pin "97") (pinfunction "CE2_97") (pintype "passive"))
      (node (ref "U3") (pin "28") (pinfunction "VCC_28") (pintype "passive"))
    )
    (net (code "75") (name "unconnected-(CN1-Pad0)") (class "Default")
      (node (ref "CN1") (pin "0") (pinfunction "0_0") (pintype "passive"))
    )
    (net (code "76") (name "unconnected-(CN2-Pad0)") (class "Default")
      (node (ref "CN2") (pin "0") (pinfunction "0_0") (pintype "passive"))
    )
    (net (code "77") (name "unconnected-(CN2-Pad15)") (class "Default")
      (node (ref "CN2") (pin "15") (pinfunction "15_15") (pintype "passive"))
    )
    (net (code "78") (name "unconnected-(CN2-Pad26)") (class "Default")
      (node (ref "CN2") (pin "26") (pinfunction "26_26") (pintype "passive"))
    )
    (net (code "79") (name "unconnected-(CN2-Pad27)") (class "Default")
      (node (ref "CN2") (pin "27") (pinfunction "27_27") (pintype "passive"))
    )
    (net (code "80") (name "unconnected-(CN2-Pad38)") (class "Default")
      (node (ref "CN2") (pin "38") (pinfunction "38_38") (pintype "passive"))
    )
    (net (code "81") (name "unconnected-(U1-(ZZ)NC-Pad64)") (class "Default")
      (node (ref "U1") (pin "64") (pinfunction "(ZZ)NC_64") (pintype "passive"))
    )
    (net (code "82") (name "unconnected-(U1-MODE-Pad31)") (class "Default")
      (node (ref "U1") (pin "31") (pinfunction "MODE_31") (pintype "passive"))
    )
    (net (code "83") (name "unconnected-(U1-NC-Pad1)") (class "Default")
      (node (ref "U1") (pin "1") (pinfunction "NC_1") (pintype "passive"))
    )
    (net (code "84") (name "unconnected-(U1-NC-Pad16)") (class "Default")
      (node (ref "U1") (pin "16") (pinfunction "NC_16") (pintype "passive"))
    )
    (net (code "85") (name "unconnected-(U1-NC-Pad30)") (class "Default")
      (node (ref "U1") (pin "30") (pinfunction "NC_30") (pintype "passive"))
    )
    (net (code "86") (name "unconnected-(U1-NC-Pad38)") (class "Default")
      (node (ref "U1") (pin "38") (pinfunction "NC_38") (pintype "passive"))
    )
    (net (code "87") (name "unconnected-(U1-NC-Pad39)") (class "Default")
      (node (ref "U1") (pin "39") (pinfunction "NC_39") (pintype "passive"))
    )
    (net (code "88") (name "unconnected-(U1-NC-Pad42)") (class "Default")
      (node (ref "U1") (pin "42") (pinfunction "NC_42") (pintype "passive"))
    )
    (net (code "89") (name "unconnected-(U1-NC-Pad43)") (class "Default")
      (node (ref "U1") (pin "43") (pinfunction "NC_43") (pintype "passive"))
    )
    (net (code "90") (name "unconnected-(U1-NC-Pad51)") (class "Default")
      (node (ref "U1") (pin "51") (pinfunction "NC_51") (pintype "passive"))
    )
    (net (code "91") (name "unconnected-(U1-NC-Pad66)") (class "Default")
      (node (ref "U1") (pin "66") (pinfunction "NC_66") (pintype "passive"))
    )
    (net (code "92") (name "unconnected-(U1-NC-Pad80)") (class "Default")
      (node (ref "U1") (pin "80") (pinfunction "NC_80") (pintype "passive"))
    )
    (net (code "93") (name "unconnected-(U2-(ZZ)NC-Pad64)") (class "Default")
      (node (ref "U2") (pin "64") (pinfunction "(ZZ)NC_64") (pintype "passive"))
    )
    (net (code "94") (name "unconnected-(U2-MODE-Pad31)") (class "Default")
      (node (ref "U2") (pin "31") (pinfunction "MODE_31") (pintype "passive"))
    )
    (net (code "95") (name "unconnected-(U2-NC-Pad1)") (class "Default")
      (node (ref "U2") (pin "1") (pinfunction "NC_1") (pintype "passive"))
    )
    (net (code "96") (name "unconnected-(U2-NC-Pad16)") (class "Default")
      (node (ref "U2") (pin "16") (pinfunction "NC_16") (pintype "passive"))
    )
    (net (code "97") (name "unconnected-(U2-NC-Pad30)") (class "Default")
      (node (ref "U2") (pin "30") (pinfunction "NC_30") (pintype "passive"))
    )
    (net (code "98") (name "unconnected-(U2-NC-Pad38)") (class "Default")
      (node (ref "U2") (pin "38") (pinfunction "NC_38") (pintype "passive"))
    )
    (net (code "99") (name "unconnected-(U2-NC-Pad39)") (class "Default")
      (node (ref "U2") (pin "39") (pinfunction "NC_39") (pintype "passive"))
    )
    (net (code "100") (name "unconnected-(U2-NC-Pad42)") (class "Default")
      (node (ref "U2") (pin "42") (pinfunction "NC_42") (pintype "passive"))
    )
    (net (code "101") (name "unconnected-(U2-NC-Pad43)") (class "Default")
      (node (ref "U2") (pin "43") (pinfunction "NC_43") (pintype "passive"))
    )
    (net (code "102") (name "unconnected-(U2-NC-Pad51)") (class "Default")
      (node (ref "U2") (pin "51") (pinfunction "NC_51") (pintype "passive"))
    )
    (net (code "103") (name "unconnected-(U2-NC-Pad66)") (class "Default")
      (node (ref "U2") (pin "66") (pinfunction "NC_66") (pintype "passive"))
    )
    (net (code "104") (name "unconnected-(U2-NC-Pad80)") (class "Default")
      (node (ref "U2") (pin "80") (pinfunction "NC_80") (pintype "passive"))
    )
  )
)
